# DSO_Power.net
KiCad netlist of a schematic drawn in Altium Designer
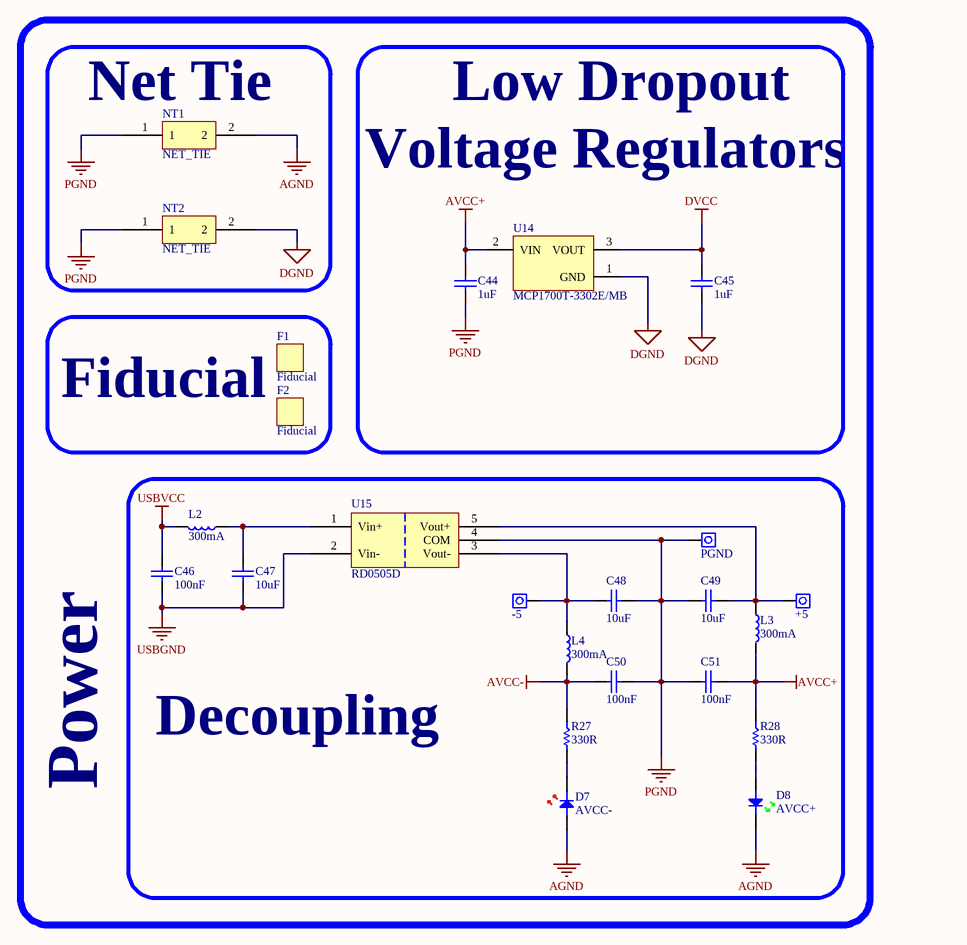
[diagram p0: DSO_Power.SchDoc]

(export (version "E")
  (design (tool "Eeschema 10.0.6"))
  (components
    (comp (ref "C44")
      (value "1uF")
      (footprint "0805C")
      (description "Capacitor")
      (fields (field (name "REVIEWED BY") "RM - 2018/08/05"))
      (libsource (lib "DSO") (part "C"))
    )
    (comp (ref "C45")
      (value "1uF")
      (footprint "0805C")
      (description "Capacitor")
      (fields (field (name "REVIEWED BY") "RM - 2018/08/05"))
      (libsource (lib "DSO") (part "C"))
    )
    (comp (ref "C46")
      (value "100nF")
      (footprint "0805C")
      (description "Capacitor")
      (fields (field (name "REVIEWED BY") "RM - 2018/08/05"))
      (libsource (lib "DSO") (part "C"))
    )
    (comp (ref "C47")
      (value "10uF")
      (footprint "0805C")
      (description "Capacitor")
      (fields (field (name "REVIEWED BY") "RM - 2018/08/05"))
      (libsource (lib "DSO") (part "C"))
    )
    (comp (ref "C48")
      (value "10uF")
      (footprint "0805C")
      (description "Capacitor")
      (fields (field (name "REVIEWED BY") "RM - 2018/08/05"))
      (libsource (lib "DSO") (part "C"))
    )
    (comp (ref "C49")
      (value "10uF")
      (footprint "0805C")
      (description "Capacitor")
      (fields (field (name "REVIEWED BY") "RM - 2018/08/05"))
      (libsource (lib "DSO") (part "C"))
    )
    (comp (ref "C50")
      (value "100nF")
      (footprint "0805C")
      (description "Capacitor")
      (fields (field (name "REVIEWED BY") "RM - 2018/08/05"))
      (libsource (lib "DSO") (part "C"))
    )
    (comp (ref "C51")
      (value "100nF")
      (footprint "0805C")
      (description "Capacitor")
      (fields (field (name "REVIEWED BY") "RM - 2018/08/05"))
      (libsource (lib "DSO") (part "C"))
    )
    (comp (ref "D7")
      (value "AVCC-")
      (footprint "0805D-RED")
      (description "Light Emitting Diode")
      (fields (field (name "REVIEWED BY") "RM - 2018/08/05"))
      (libsource (lib "DSO") (part "LED RED"))
    )
    (comp (ref "D8")
      (value "AVCC+")
      (footprint "0805D-GREEN")
      (description "Light Emitting Diode")
      (fields (field (name "REVIEWED BY") "RM - 2018/08/05"))
      (libsource (lib "DSO") (part "LED GREEN"))
    )
    (comp (ref "F1") (value "Fiducial") (footprint "Fiducial") (libsource (lib "DSO") (part "Fiducial")))
    (comp (ref "F2") (value "Fiducial") (footprint "Fiducial") (libsource (lib "DSO") (part "Fiducial")))
    (comp (ref "L2")
      (value "300mA")
      (footprint "0805")
      (description "Inductor")
      (fields (field (name "REVIEWED BY") "RM - 2018/08/05"))
      (libsource (lib "DSO") (part "I"))
    )
    (comp (ref "L3")
      (value "300mA")
      (footprint "0805")
      (description "Inductor")
      (fields (field (name "REVIEWED BY") "RM - 2018/08/05"))
      (libsource (lib "DSO") (part "I"))
    )
    (comp (ref "L4")
      (value "300mA")
      (footprint "0805")
      (description "Inductor")
      (fields (field (name "REVIEWED BY") "RM - 2018/08/05"))
      (libsource (lib "DSO") (part "I"))
    )
    (comp (ref "NT1")
      (value "NET_TIE")
      (footprint "NET_TIE")
      (description "Net Tie")
      (libsource (lib "DSO") (part "NET_TIE"))
    )
    (comp (ref "NT2")
      (value "NET_TIE")
      (footprint "NET_TIE")
      (description "Net Tie")
      (libsource (lib "DSO") (part "NET_TIE"))
    )
    (comp (ref "R27")
      (value "330R")
      (footprint "0805")
      (description "Resistor")
      (fields (field (name "REVIEWED BY") "RM - 2018/08/05"))
      (libsource (lib "DSO") (part "R"))
    )
    (comp (ref "R28")
      (value "330R")
      (footprint "0805")
      (description "Resistor")
      (fields (field (name "REVIEWED BY") "RM - 2018/08/05"))
      (libsource (lib "DSO") (part "R"))
    )
    (comp (ref "TP8")
      (value "PGND")
      (footprint "PIN 1.8mm")
      (description "Pad")
      (libsource (lib "DSO") (part "WIRE"))
    )
    (comp (ref "TP9")
      (value "-5")
      (footprint "PIN 1.8mm")
      (description "Pad")
      (libsource (lib "DSO") (part "WIRE"))
    )
    (comp (ref "TP10")
      (value "+5")
      (footprint "PIN 1.8mm")
      (description "Pad")
      (libsource (lib "DSO") (part "WIRE"))
    )
    (comp (ref "U14")
      (value "MCP1700T-3302E/MB")
      (footprint "SOT89")
      (description "Low Quiescent Current LDO, 3-Pin SOT-89, Extended Temperature, Tape and Reel")
      (fields (field (name "REVIEWED BY") "RM - 2018/08/05"))
      (libsource (lib "DSO") (part "MCP1700T"))
    )
    (comp (ref "U15")
      (value "RD0505D")
      (footprint "SIP_NMG")
      (description "(ADV) DC to DC converter 5V in +-5V out")
      (fields (field (name "REVIEWED BY") "RM - 2018/08/05"))
      (libsource (lib "DSO") (part "RD0505D"))
    )
  )
  (nets
    (net (code "1") (name "AGND") (class "Default")
      (node (ref "D7") (pin "A") (pinfunction "A_A") (pintype "passive"))
      (node (ref "D8") (pin "K") (pinfunction "K_K") (pintype "passive"))
      (node (ref "NT1") (pin "2") (pinfunction "2_2") (pintype "passive"))
    )
    (net (code "2") (name "AVCC+") (class "Default")
      (node (ref "C44") (pin "2") (pinfunction "2_2") (pintype "passive"))
      (node (ref "C51") (pin "1") (pinfunction "1_1") (pintype "passive"))
      (node (ref "L3") (pin "2") (pinfunction "2_2") (pintype "passive"))
      (node (ref "R28") (pin "1") (pintype "passive"))
      (node (ref "U14") (pin "2") (pinfunction "VIN_2") (pintype "power_in"))
    )
    (net (code "3") (name "AVCC-") (class "Default")
      (node (ref "C50") (pin "2") (pinfunction "2_2") (pintype "passive"))
      (node (ref "L4") (pin "2") (pinfunction "2_2") (pintype "passive"))
      (node (ref "R27") (pin "1") (pintype "passive"))
    )
    (net (code "4") (name "DGND") (class "Default")
      (node (ref "C45") (pin "1") (pinfunction "1_1") (pintype "passive"))
      (node (ref "NT2") (pin "2") (pinfunction "2_2") (pintype "passive"))
      (node (ref "U14") (pin "1") (pinfunction "GND_1") (pintype "power_in"))
    )
    (net (code "5") (name "DVCC") (class "Default")
      (node (ref "C45") (pin "2") (pinfunction "2_2") (pintype "passive"))
      (node (ref "U14") (pin "3") (pinfunction "VOUT_3") (pintype "power_in"))
    )
    (net (code "6") (name "Net-(D7-PadK)") (class "Default")
      (node (ref "D7") (pin "K") (pinfunction "K_K") (pintype "passive"))
      (node (ref "R27") (pin "2") (pintype "passive"))
    )
    (net (code "7") (name "Net-(D8-PadA)") (class "Default")
      (node (ref "D8") (pin "A") (pinfunction "A_A") (pintype "passive"))
      (node (ref "R28") (pin "2") (pintype "passive"))
    )
    (net (code "8") (name "Net-(U15-Vin+)") (class "Default")
      (node (ref "C47") (pin "2") (pinfunction "2_2") (pintype "passive"))
      (node (ref "L2") (pin "1") (pinfunction "1_1") (pintype "passive"))
      (node (ref "U15") (pin "1") (pinfunction "Vin+_1") (pintype "passive"))
    )
    (net (code "9") (name "Net-(U15-Vout+)") (class "Default")
      (node (ref "C49") (pin "1") (pinfunction "1_1") (pintype "passive"))
      (node (ref "L3") (pin "1") (pinfunction "1_1") (pintype "passive"))
      (node (ref "TP10") (pin "1") (pintype "passive"))
      (node (ref "U15") (pin "5") (pinfunction "Vout+_5") (pintype "passive"))
    )
    (net (code "10") (name "Net-(U15-Vout-)") (class "Default")
      (node (ref "C48") (pin "2") (pinfunction "2_2") (pintype "passive"))
      (node (ref "L4") (pin "1") (pinfunction "1_1") (pintype "passive"))
      (node (ref "TP9") (pin "1") (pintype "passive"))
      (node (ref "U15") (pin "3") (pinfunction "Vout-_3") (pintype "passive"))
    )
    (net (code "11") (name "PGND") (class "Default")
      (node (ref "C44") (pin "1") (pinfunction "1_1") (pintype "passive"))
      (node (ref "C48") (pin "1") (pinfunction "1_1") (pintype "passive"))
      (node (ref "C49") (pin "2") (pinfunction "2_2") (pintype "passive"))
      (node (ref "C50") (pin "1") (pinfunction "1_1") (pintype "passive"))
      (node (ref "C51") (pin "2") (pinfunction "2_2") (pintype "passive"))
      (node (ref "NT1") (pin "1") (pinfunction "1_1") (pintype "passive"))
      (node (ref "NT2") (pin "1") (pinfunction "1_1") (pintype "passive"))
      (node (ref "TP8") (pin "1") (pintype "passive"))
      (node (ref "U15") (pin "4") (pinfunction "COM_4") (pintype "passive"))
    )
    (net (code "12") (name "USBGND") (class "Default")
      (node (ref "C46") (pin "1") (pinfunction "1_1") (pintype "passive"))
      (node (ref "C47") (pin "1") (pinfunction "1_1") (pintype "passive"))
      (node (ref "U15") (pin "2") (pinfunction "Vin-_2") (pintype "passive"))
    )
    (net (code "13") (name "USBVCC") (class "Default")
      (node (ref "C46") (pin "2") (pinfunction "2_2") (pintype "passive"))
      (node (ref "L2") (pin "2") (pinfunction "2_2") (pintype "passive"))
    )
  )
)
